# NeatoLDS_Breakout_Board_v1_0.net
KiCad netlist of a schematic drawn in EAGLE
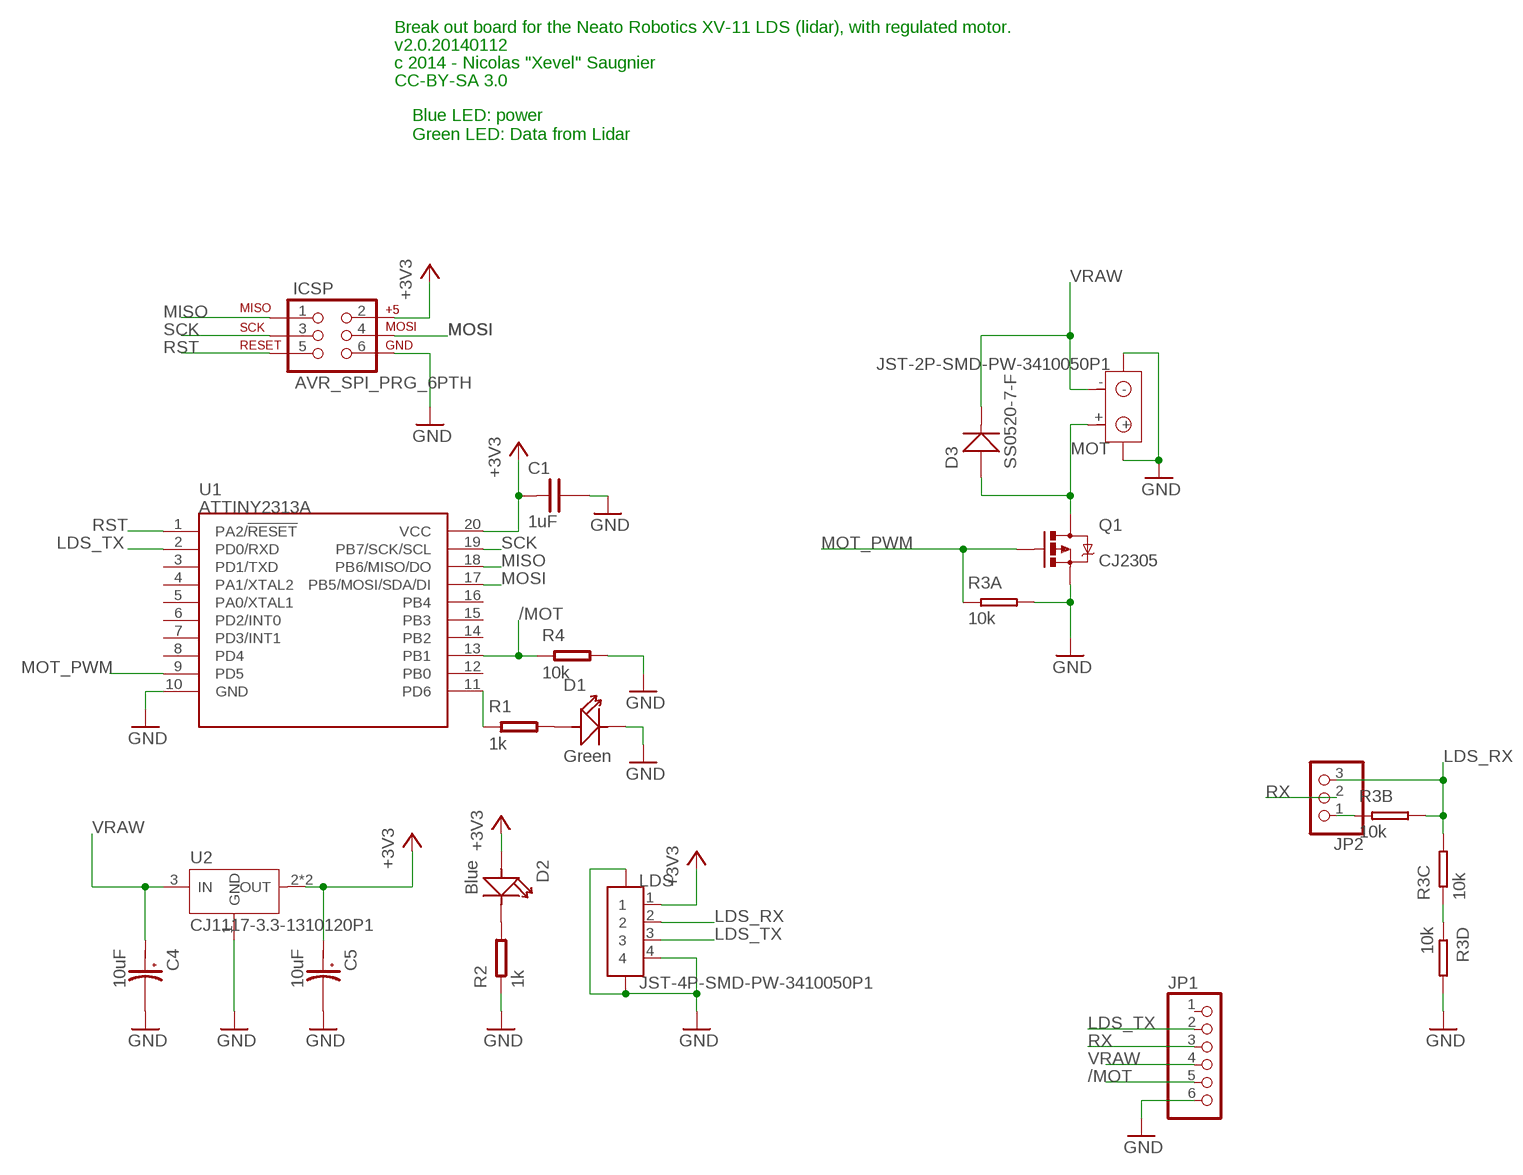
[diagram p0: schematic, sheet 1]

(export (version "E")
  (design (tool "Eeschema 10.0.6"))
  (components
    (comp (ref "C1")
      (value "1uF")
      (footprint "eagle-import:C0603")
      (libsource (lib "eagle-import") (part "C-0603"))
    )
    (comp (ref "C4")
      (value "10uF")
      (footprint "eagle-import:AVX-A")
      (libsource (lib "eagle-import") (part "C-POLAR-A"))
    )
    (comp (ref "C5")
      (value "10uF")
      (footprint "eagle-import:AVX-A")
      (libsource (lib "eagle-import") (part "C-POLAR-A"))
    )
    (comp (ref "D1")
      (value "Green")
      (footprint "eagle-import:LED0603")
      (libsource (lib "eagle-import") (part "LED"))
    )
    (comp (ref "D2")
      (value "Blue")
      (footprint "eagle-import:LED0603")
      (libsource (lib "eagle-import") (part "LED"))
    )
    (comp (ref "D3")
      (value "SS0520-7-F")
      (footprint "eagle-import:SOD123")
      (libsource (lib "eagle-import") (part "D-SOD-123"))
    )
    (comp (ref "ICSP")
      (value "AVR_SPI_PRG_6PTH")
      (footprint "eagle-import:2X3")
      (libsource (lib "eagle-import") (part "AVR_SPI_PRG_6PTH"))
    )
    (comp (ref "JP1")
      (value "PINHD-1X6")
      (footprint "eagle-import:1X06")
      (libsource (lib "eagle-import") (part "PINHD-1X6"))
    )
    (comp (ref "JP2")
      (value "PINHD-1X3")
      (footprint "eagle-import:1X03")
      (libsource (lib "eagle-import") (part "PINHD-1X3"))
    )
    (comp (ref "LDS")
      (value "JST-4P-SMD-PW-3410050P1")
      (footprint "eagle-import:CON-4P-SMD-2.0-90D")
      (libsource (lib "eagle-import") (part "JST-4P-SMD-PW-3410050P1"))
    )
    (comp (ref "MOT")
      (value "JST-2P-SMD-PW-3410050P1")
      (footprint "eagle-import:2P-SMD-2.0-90D")
      (libsource (lib "eagle-import") (part "JST-2P-SMD-PW-3410050P1"))
    )
    (comp (ref "Q1")
      (value "CJ2305")
      (footprint "eagle-import:SOT-23-3_N_SSOT-3_N")
      (libsource (lib "eagle-import") (part "MOSFET_P_FDN308P"))
    )
    (comp (ref "R1")
      (value "1k")
      (footprint "eagle-import:R0603")
      (libsource (lib "eagle-import") (part "R-0603"))
    )
    (comp (ref "R2")
      (value "1k")
      (footprint "eagle-import:R0603")
      (libsource (lib "eagle-import") (part "R-0603"))
    )
    (comp (ref "R3")
      (value "10k")
      (footprint "eagle-import:R1206-8")
      (libsource (lib "eagle-import") (part "R-4R"))
    )
    (comp (ref "R4")
      (value "10k")
      (footprint "eagle-import:R0603")
      (libsource (lib "eagle-import") (part "R-0603"))
    )
    (comp (ref "U1")
      (value "ATTINY2313A")
      (footprint "eagle-import:SOP20W")
      (libsource (lib "eagle-import") (part "ATTINY2313A"))
    )
    (comp (ref "U2")
      (value "CJ1117-3.3-1310120P1")
      (footprint "eagle-import:SOT89")
      (libsource (lib "eagle-import") (part "CJ1117-3.3-1310120P1"))
    )
  )
  (nets
    (net (code "1") (name "+3V3") (class "Default")
      (node (ref "C1") (pin "1") (pinfunction "1_1") (pintype "passive"))
      (node (ref "C5") (pin "+") (pinfunction "1_+") (pintype "bidirectional"))
      (node (ref "D2") (pin "+") (pinfunction "+_+") (pintype "passive"))
      (node (ref "ICSP") (pin "2") (pinfunction "2_2") (pintype "passive"))
      (node (ref "LDS") (pin "1") (pinfunction "1_1") (pintype "bidirectional"))
      (node (ref "U1") (pin "20") (pinfunction "VCC_20") (pintype "bidirectional"))
      (node (ref "U2") (pin "2") (pinfunction "OUT_2") (pintype "bidirectional"))
      (node (ref "U2") (pin "4") (pinfunction "OUT_4") (pintype "bidirectional"))
    )
    (net (code "2") (name "/LDS_RX") (class "Default")
      (node (ref "JP2") (pin "3") (pinfunction "3_3") (pintype "passive"))
      (node (ref "LDS") (pin "2") (pinfunction "2_2") (pintype "bidirectional"))
      (node (ref "R3") (pin "6") (pinfunction "2_6") (pintype "passive"))
      (node (ref "R3") (pin "7") (pinfunction "2_7") (pintype "passive"))
    )
    (net (code "3") (name "/LDS_TX") (class "Default")
      (node (ref "JP1") (pin "2") (pinfunction "2_2") (pintype "passive"))
      (node (ref "LDS") (pin "3") (pinfunction "3_3") (pintype "bidirectional"))
      (node (ref "U1") (pin "2") (pinfunction "PD0/RXD_2") (pintype "bidirectional"))
    )
    (net (code "4") (name "/MISO") (class "Default")
      (node (ref "ICSP") (pin "1") (pinfunction "1_1") (pintype "passive"))
      (node (ref "U1") (pin "18") (pinfunction "PB6/MISO/DO_18") (pintype "bidirectional"))
    )
    (net (code "5") (name "/MOSI") (class "Default")
      (node (ref "ICSP") (pin "4") (pinfunction "4_4") (pintype "passive"))
      (node (ref "U1") (pin "17") (pinfunction "PB5/MOSI/SDA/DI_17") (pintype "bidirectional"))
    )
    (net (code "6") (name "/MOT_PWM") (class "Default")
      (node (ref "Q1") (pin "1") (pinfunction "G_1") (pintype "passive"))
      (node (ref "R3") (pin "1") (pinfunction "1_1") (pintype "passive"))
      (node (ref "U1") (pin "9") (pinfunction "PD5_9") (pintype "bidirectional"))
    )
    (net (code "7") (name "/RST") (class "Default")
      (node (ref "ICSP") (pin "5") (pinfunction "5_5") (pintype "passive"))
      (node (ref "U1") (pin "1") (pinfunction "PA2/~{RESET}_1") (pintype "bidirectional"))
    )
    (net (code "8") (name "/RX") (class "Default")
      (node (ref "JP1") (pin "3") (pinfunction "3_3") (pintype "passive"))
      (node (ref "JP2") (pin "2") (pinfunction "2_2") (pintype "passive"))
    )
    (net (code "9") (name "/SCK") (class "Default")
      (node (ref "ICSP") (pin "3") (pinfunction "3_3") (pintype "passive"))
      (node (ref "U1") (pin "19") (pinfunction "PB7/SCK/SCL_19") (pintype "bidirectional"))
    )
    (net (code "10") (name "/VRAW") (class "Default")
      (node (ref "C4") (pin "+") (pinfunction "1_+") (pintype "bidirectional"))
      (node (ref "D3") (pin "-") (pinfunction "-_-") (pintype "passive"))
      (node (ref "JP1") (pin "4") (pinfunction "4_4") (pintype "passive"))
      (node (ref "MOT") (pin "-") (pinfunction "-_-") (pintype "bidirectional"))
      (node (ref "U2") (pin "3") (pinfunction "IN_3") (pintype "bidirectional"))
    )
    (net (code "11") (name "/{slash}MOT") (class "Default")
      (node (ref "JP1") (pin "5") (pinfunction "5_5") (pintype "passive"))
      (node (ref "R4") (pin "1") (pinfunction "1_1") (pintype "passive"))
      (node (ref "U1") (pin "13") (pinfunction "PB1_13") (pintype "bidirectional"))
    )
    (net (code "12") (name "GND") (class "Default")
      (node (ref "C1") (pin "2") (pinfunction "2_2") (pintype "passive"))
      (node (ref "C4") (pin "-") (pinfunction "2_-") (pintype "bidirectional"))
      (node (ref "C5") (pin "-") (pinfunction "2_-") (pintype "bidirectional"))
      (node (ref "D1") (pin "-") (pinfunction "-_-") (pintype "passive"))
      (node (ref "ICSP") (pin "6") (pinfunction "6_6") (pintype "passive"))
      (node (ref "JP1") (pin "6") (pinfunction "6_6") (pintype "passive"))
      (node (ref "LDS") (pin "4") (pinfunction "4_4") (pintype "bidirectional"))
      (node (ref "LDS") (pin "5") (pinfunction "5_5") (pintype "bidirectional"))
      (node (ref "LDS") (pin "6") (pinfunction "6_6") (pintype "bidirectional"))
      (node (ref "MOT") (pin "3") (pinfunction "3_3") (pintype "bidirectional"))
      (node (ref "MOT") (pin "4") (pinfunction "4_4") (pintype "bidirectional"))
      (node (ref "Q1") (pin "2") (pinfunction "S_2") (pintype "passive"))
      (node (ref "R2") (pin "1") (pinfunction "1_1") (pintype "passive"))
      (node (ref "R3") (pin "5") (pinfunction "2_5") (pintype "passive"))
      (node (ref "R3") (pin "8") (pinfunction "2_8") (pintype "passive"))
      (node (ref "R4") (pin "2") (pinfunction "2_2") (pintype "passive"))
      (node (ref "U1") (pin "10") (pinfunction "GND_10") (pintype "bidirectional"))
      (node (ref "U2") (pin "1") (pinfunction "GND_1") (pintype "bidirectional"))
    )
    (net (code "13") (name "Net-(D1-Pad+)") (class "Default")
      (node (ref "D1") (pin "+") (pinfunction "+_+") (pintype "passive"))
      (node (ref "R1") (pin "2") (pinfunction "2_2") (pintype "passive"))
    )
    (net (code "14") (name "Net-(D2-Pad-)") (class "Default")
      (node (ref "D2") (pin "-") (pinfunction "-_-") (pintype "passive"))
      (node (ref "R2") (pin "2") (pinfunction "2_2") (pintype "passive"))
    )
    (net (code "15") (name "Net-(Q1-D)") (class "Default")
      (node (ref "D3") (pin "+") (pinfunction "+_+") (pintype "passive"))
      (node (ref "MOT") (pin "+") (pinfunction "+_+") (pintype "bidirectional"))
      (node (ref "Q1") (pin "3") (pinfunction "D_3") (pintype "passive"))
    )
    (net (code "16") (name "Net-(R3B-1)") (class "Default")
      (node (ref "JP2") (pin "1") (pinfunction "1_1") (pintype "passive"))
      (node (ref "R3") (pin "2") (pinfunction "1_2") (pintype "passive"))
    )
    (net (code "17") (name "Net-(R3C-1)") (class "Default")
      (node (ref "R3") (pin "3") (pinfunction "1_3") (pintype "passive"))
      (node (ref "R3") (pin "4") (pinfunction "1_4") (pintype "passive"))
    )
    (net (code "18") (name "Net-(U1-PD6)") (class "Default")
      (node (ref "R1") (pin "1") (pinfunction "1_1") (pintype "passive"))
      (node (ref "U1") (pin "11") (pinfunction "PD6_11") (pintype "bidirectional"))
    )
    (net (code "19") (name "unconnected-(JP1-Pad1)") (class "Default")
      (node (ref "JP1") (pin "1") (pinfunction "1_1") (pintype "passive"))
    )
    (net (code "20") (name "unconnected-(U1-PA0{slash}XTAL1-Pad5)") (class "Default")
      (node (ref "U1") (pin "5") (pinfunction "PA0/XTAL1_5") (pintype "bidirectional"))
    )
    (net (code "21") (name "unconnected-(U1-PA1{slash}XTAL2-Pad4)") (class "Default")
      (node (ref "U1") (pin "4") (pinfunction "PA1/XTAL2_4") (pintype "bidirectional"))
    )
    (net (code "22") (name "unconnected-(U1-PB0-Pad12)") (class "Default")
      (node (ref "U1") (pin "12") (pinfunction "PB0_12") (pintype "bidirectional"))
    )
    (net (code "23") (name "unconnected-(U1-PB2-Pad14)") (class "Default")
      (node (ref "U1") (pin "14") (pinfunction "PB2_14") (pintype "bidirectional"))
    )
    (net (code "24") (name "unconnected-(U1-PB3-Pad15)") (class "Default")
      (node (ref "U1") (pin "15") (pinfunction "PB3_15") (pintype "bidirectional"))
    )
    (net (code "25") (name "unconnected-(U1-PB4-Pad16)") (class "Default")
      (node (ref "U1") (pin "16") (pinfunction "PB4_16") (pintype "bidirectional"))
    )
    (net (code "26") (name "unconnected-(U1-PD1{slash}TXD-Pad3)") (class "Default")
      (node (ref "U1") (pin "3") (pinfunction "PD1/TXD_3") (pintype "bidirectional"))
    )
    (net (code "27") (name "unconnected-(U1-PD2{slash}INT0-Pad6)") (class "Default")
      (node (ref "U1") (pin "6") (pinfunction "PD2/INT0_6") (pintype "bidirectional"))
    )
    (net (code "28") (name "unconnected-(U1-PD3{slash}INT1-Pad7)") (class "Default")
      (node (ref "U1") (pin "7") (pinfunction "PD3/INT1_7") (pintype "bidirectional"))
    )
    (net (code "29") (name "unconnected-(U1-PD4-Pad8)") (class "Default")
      (node (ref "U1") (pin "8") (pinfunction "PD4_8") (pintype "bidirectional"))
    )
  )
)
